# flex_probe.net
KiCad netlist of a schematic drawn in EAGLE
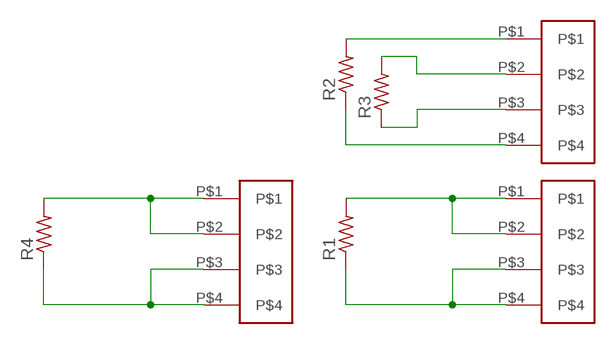
[diagram p0: schematic, sheet 1]

(export (version "E")
  (design (tool "Eeschema 10.0.6"))
  (components
    (comp (ref "R1")
      (value "R-US_R0603")
      (footprint "eagle-import:R0603")
      (libsource (lib "eagle-import") (part "R-US_R0603"))
    )
    (comp (ref "R2")
      (value "R-US_R0603")
      (footprint "eagle-import:R0603")
      (libsource (lib "eagle-import") (part "R-US_R0603"))
    )
    (comp (ref "R3")
      (value "R-US_R0603")
      (footprint "eagle-import:R0603")
      (libsource (lib "eagle-import") (part "R-US_R0603"))
    )
    (comp (ref "R4")
      (value "R-US_R0603")
      (footprint "eagle-import:R0603")
      (libsource (lib "eagle-import") (part "R-US_R0603"))
    )
    (comp (ref "U$1")
      (value "CONN_1X4")
      (footprint "eagle-import:4PAD")
      (libsource (lib "eagle-import") (part "CONN_1X4"))
    )
    (comp (ref "U$2")
      (value "CONN_1X4")
      (footprint "eagle-import:4PAD")
      (libsource (lib "eagle-import") (part "CONN_1X4"))
    )
    (comp (ref "U$3")
      (value "CONN_1X4")
      (footprint "eagle-import:4PAD")
      (libsource (lib "eagle-import") (part "CONN_1X4"))
    )
  )
  (nets
    (net (code "1") (name "Net-(R1-Pad1)") (class "Default")
      (node (ref "R1") (pin "1") (pinfunction "1_1") (pintype "passive"))
      (node (ref "U$1") (pin "P$3") (pinfunction "P$3_P$3") (pintype "bidirectional"))
      (node (ref "U$1") (pin "P$4") (pinfunction "P$4_P$4") (pintype "bidirectional"))
    )
    (net (code "2") (name "Net-(R1-Pad2)") (class "Default")
      (node (ref "R1") (pin "2") (pinfunction "2_2") (pintype "passive"))
      (node (ref "U$1") (pin "P$1") (pinfunction "P$1_P$1") (pintype "bidirectional"))
      (node (ref "U$1") (pin "P$2") (pinfunction "P$2_P$2") (pintype "bidirectional"))
    )
    (net (code "3") (name "Net-(R2-Pad1)") (class "Default")
      (node (ref "R2") (pin "1") (pinfunction "1_1") (pintype "passive"))
      (node (ref "U$2") (pin "P$4") (pinfunction "P$4_P$4") (pintype "bidirectional"))
    )
    (net (code "4") (name "Net-(R2-Pad2)") (class "Default")
      (node (ref "R2") (pin "2") (pinfunction "2_2") (pintype "passive"))
      (node (ref "U$2") (pin "P$1") (pinfunction "P$1_P$1") (pintype "bidirectional"))
    )
    (net (code "5") (name "Net-(R3-Pad1)") (class "Default")
      (node (ref "R3") (pin "1") (pinfunction "1_1") (pintype "passive"))
      (node (ref "U$2") (pin "P$3") (pinfunction "P$3_P$3") (pintype "bidirectional"))
    )
    (net (code "6") (name "Net-(R3-Pad2)") (class "Default")
      (node (ref "R3") (pin "2") (pinfunction "2_2") (pintype "passive"))
      (node (ref "U$2") (pin "P$2") (pinfunction "P$2_P$2") (pintype "bidirectional"))
    )
    (net (code "7") (name "Net-(R4-Pad1)") (class "Default")
      (node (ref "R4") (pin "1") (pinfunction "1_1") (pintype "passive"))
      (node (ref "U$3") (pin "P$3") (pinfunction "P$3_P$3") (pintype "bidirectional"))
      (node (ref "U$3") (pin "P$4") (pinfunction "P$4_P$4") (pintype "bidirectional"))
    )
    (net (code "8") (name "Net-(R4-Pad2)") (class "Default")
      (node (ref "R4") (pin "2") (pinfunction "2_2") (pintype "passive"))
      (node (ref "U$3") (pin "P$1") (pinfunction "P$1_P$1") (pintype "bidirectional"))
      (node (ref "U$3") (pin "P$2") (pinfunction "P$2_P$2") (pintype "bidirectional"))
    )
  )
)
